# R151D.net
KiCad netlist of a schematic drawn in EAGLE
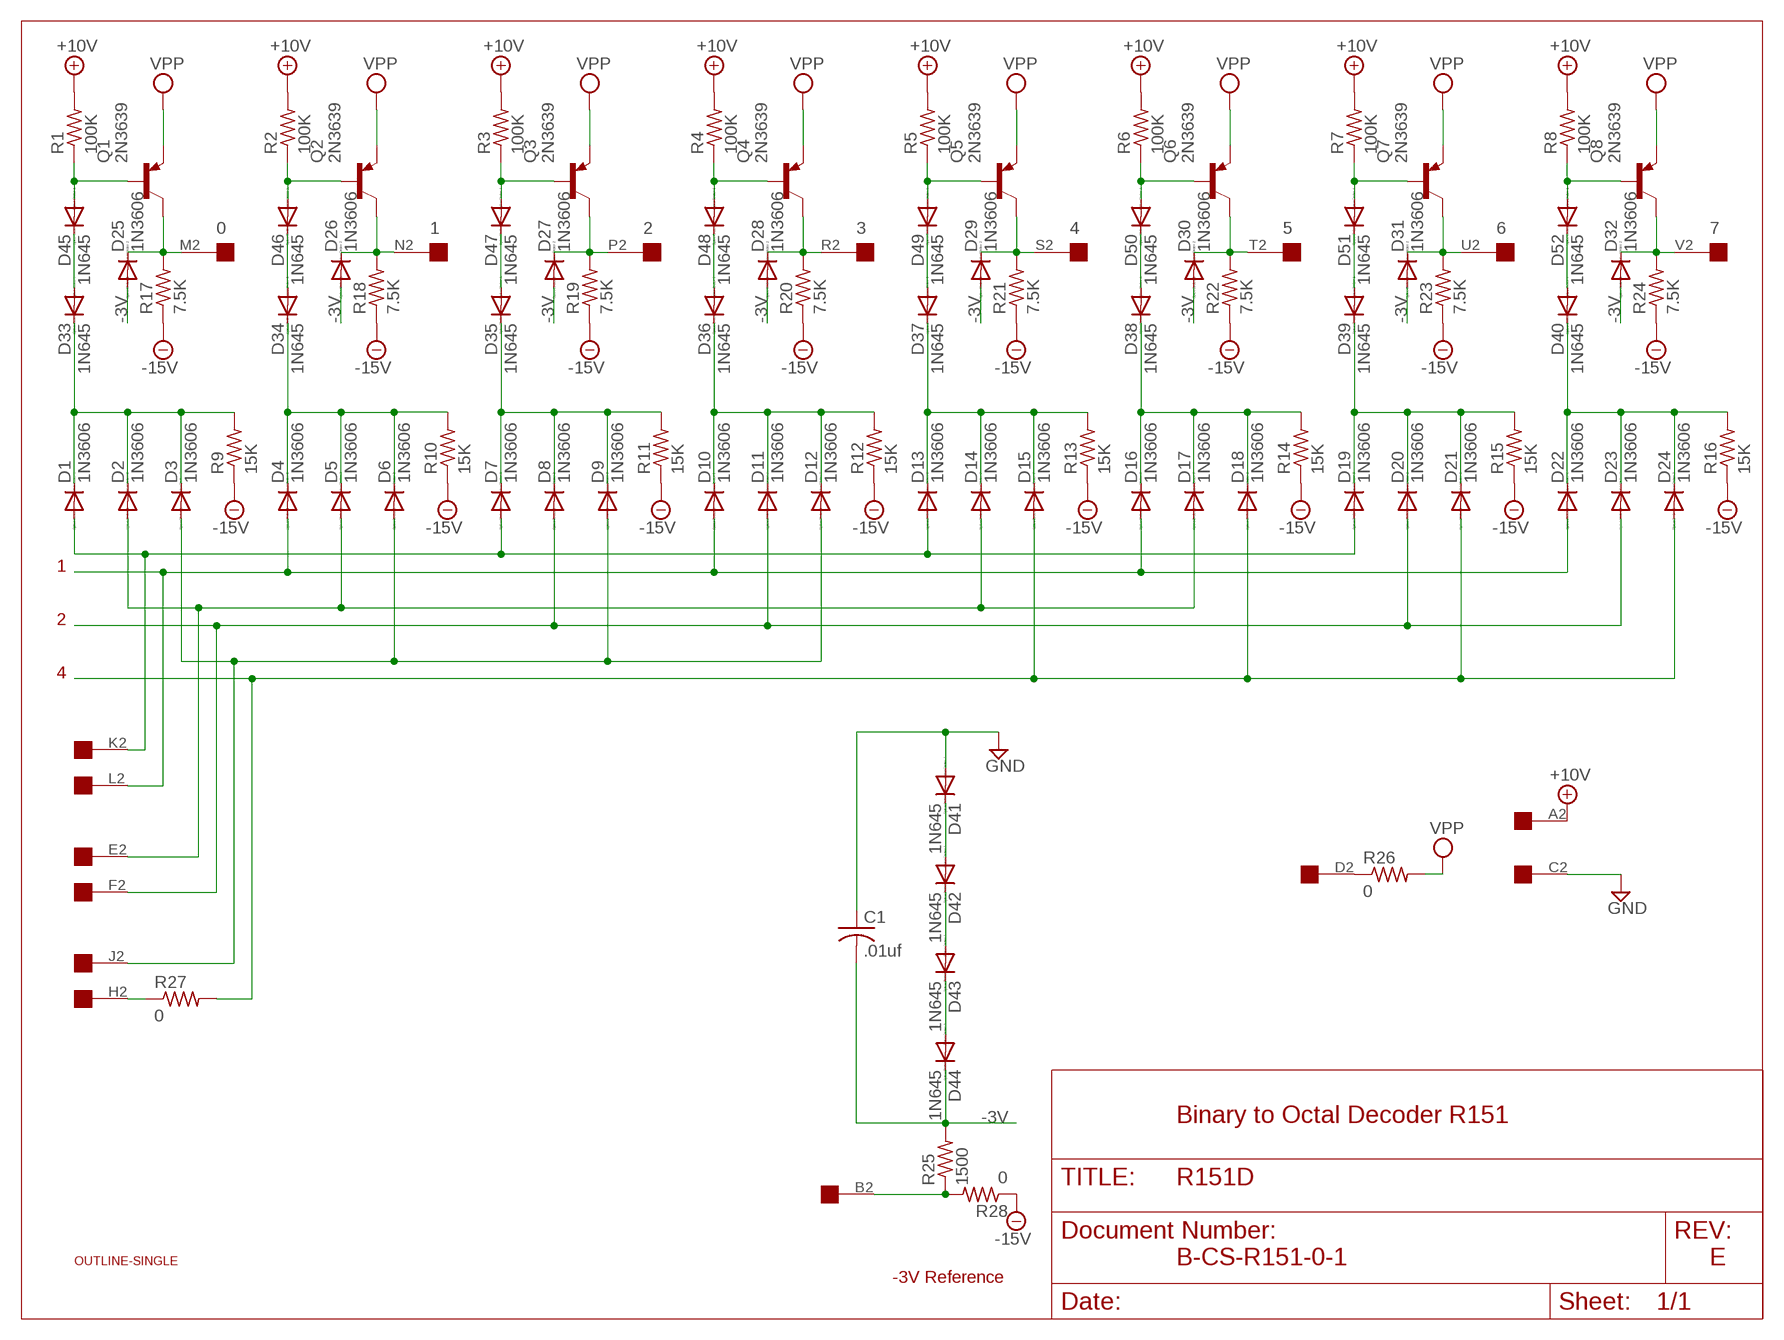
[diagram p0: schematic, sheet 1]

(export (version "E")
  (design (tool "Eeschema 10.0.6"))
  (components
    (comp (ref "C1")
      (value ".01uf")
      (footprint "eagle-import:C050-025X075")
      (libsource (lib "eagle-import") (part "C-US050-025X075"))
    )
    (comp (ref "D1")
      (value "1N3606")
      (footprint "eagle-import:DO35-10")
      (libsource (lib "eagle-import") (part "1N4148DO35-10"))
    )
    (comp (ref "D2")
      (value "1N3606")
      (footprint "eagle-import:DO35-10")
      (libsource (lib "eagle-import") (part "1N4148DO35-10"))
    )
    (comp (ref "D3")
      (value "1N3606")
      (footprint "eagle-import:DO35-10")
      (libsource (lib "eagle-import") (part "1N4148DO35-10"))
    )
    (comp (ref "D4")
      (value "1N3606")
      (footprint "eagle-import:DO35-10")
      (libsource (lib "eagle-import") (part "1N4148DO35-10"))
    )
    (comp (ref "D5")
      (value "1N3606")
      (footprint "eagle-import:DO35-10")
      (libsource (lib "eagle-import") (part "1N4148DO35-10"))
    )
    (comp (ref "D6")
      (value "1N3606")
      (footprint "eagle-import:DO35-10")
      (libsource (lib "eagle-import") (part "1N4148DO35-10"))
    )
    (comp (ref "D7")
      (value "1N3606")
      (footprint "eagle-import:DO35-10")
      (libsource (lib "eagle-import") (part "1N4148DO35-10"))
    )
    (comp (ref "D8")
      (value "1N3606")
      (footprint "eagle-import:DO35-10")
      (libsource (lib "eagle-import") (part "1N4148DO35-10"))
    )
    (comp (ref "D9")
      (value "1N3606")
      (footprint "eagle-import:DO35-10")
      (libsource (lib "eagle-import") (part "1N4148DO35-10"))
    )
    (comp (ref "D10")
      (value "1N3606")
      (footprint "eagle-import:DO35-10")
      (libsource (lib "eagle-import") (part "1N4148DO35-10"))
    )
    (comp (ref "D11")
      (value "1N3606")
      (footprint "eagle-import:DO35-10")
      (libsource (lib "eagle-import") (part "1N4148DO35-10"))
    )
    (comp (ref "D12")
      (value "1N3606")
      (footprint "eagle-import:DO35-10")
      (libsource (lib "eagle-import") (part "1N4148DO35-10"))
    )
    (comp (ref "D13")
      (value "1N3606")
      (footprint "eagle-import:DO35-10")
      (libsource (lib "eagle-import") (part "1N4148DO35-10"))
    )
    (comp (ref "D14")
      (value "1N3606")
      (footprint "eagle-import:DO35-10")
      (libsource (lib "eagle-import") (part "1N4148DO35-10"))
    )
    (comp (ref "D15")
      (value "1N3606")
      (footprint "eagle-import:DO35-10")
      (libsource (lib "eagle-import") (part "1N4148DO35-10"))
    )
    (comp (ref "D16")
      (value "1N3606")
      (footprint "eagle-import:DO35-10")
      (libsource (lib "eagle-import") (part "1N4148DO35-10"))
    )
    (comp (ref "D17")
      (value "1N3606")
      (footprint "eagle-import:DO35-10")
      (libsource (lib "eagle-import") (part "1N4148DO35-10"))
    )
    (comp (ref "D18")
      (value "1N3606")
      (footprint "eagle-import:DO35-10")
      (libsource (lib "eagle-import") (part "1N4148DO35-10"))
    )
    (comp (ref "D19")
      (value "1N3606")
      (footprint "eagle-import:DO35-10")
      (libsource (lib "eagle-import") (part "1N4148DO35-10"))
    )
    (comp (ref "D20")
      (value "1N3606")
      (footprint "eagle-import:DO35-10")
      (libsource (lib "eagle-import") (part "1N4148DO35-10"))
    )
    (comp (ref "D21")
      (value "1N3606")
      (footprint "eagle-import:DO35-10")
      (libsource (lib "eagle-import") (part "1N4148DO35-10"))
    )
    (comp (ref "D22")
      (value "1N3606")
      (footprint "eagle-import:DO35-10")
      (libsource (lib "eagle-import") (part "1N4148DO35-10"))
    )
    (comp (ref "D23")
      (value "1N3606")
      (footprint "eagle-import:DO35-10")
      (libsource (lib "eagle-import") (part "1N4148DO35-10"))
    )
    (comp (ref "D24")
      (value "1N3606")
      (footprint "eagle-import:DO35-10")
      (libsource (lib "eagle-import") (part "1N4148DO35-10"))
    )
    (comp (ref "D25")
      (value "1N3606")
      (footprint "eagle-import:DO35-10")
      (libsource (lib "eagle-import") (part "1N4148DO35-10"))
    )
    (comp (ref "D26")
      (value "1N3606")
      (footprint "eagle-import:DO35-10")
      (libsource (lib "eagle-import") (part "1N4148DO35-10"))
    )
    (comp (ref "D27")
      (value "1N3606")
      (footprint "eagle-import:DO35-10")
      (libsource (lib "eagle-import") (part "1N4148DO35-10"))
    )
    (comp (ref "D28")
      (value "1N3606")
      (footprint "eagle-import:DO35-10")
      (libsource (lib "eagle-import") (part "1N4148DO35-10"))
    )
    (comp (ref "D29")
      (value "1N3606")
      (footprint "eagle-import:DO35-10")
      (libsource (lib "eagle-import") (part "1N4148DO35-10"))
    )
    (comp (ref "D30")
      (value "1N3606")
      (footprint "eagle-import:DO35-10")
      (libsource (lib "eagle-import") (part "1N4148DO35-10"))
    )
    (comp (ref "D31")
      (value "1N3606")
      (footprint "eagle-import:DO35-10")
      (libsource (lib "eagle-import") (part "1N4148DO35-10"))
    )
    (comp (ref "D32")
      (value "1N3606")
      (footprint "eagle-import:DO35-10")
      (libsource (lib "eagle-import") (part "1N4148DO35-10"))
    )
    (comp (ref "D33")
      (value "1N645")
      (footprint "eagle-import:DO35-10")
      (libsource (lib "eagle-import") (part "1N4148DO35-10"))
    )
    (comp (ref "D34")
      (value "1N645")
      (footprint "eagle-import:DO35-10")
      (libsource (lib "eagle-import") (part "1N4148DO35-10"))
    )
    (comp (ref "D35")
      (value "1N645")
      (footprint "eagle-import:DO35-10")
      (libsource (lib "eagle-import") (part "1N4148DO35-10"))
    )
    (comp (ref "D36")
      (value "1N645")
      (footprint "eagle-import:DO35-10")
      (libsource (lib "eagle-import") (part "1N4148DO35-10"))
    )
    (comp (ref "D37")
      (value "1N645")
      (footprint "eagle-import:DO35-10")
      (libsource (lib "eagle-import") (part "1N4148DO35-10"))
    )
    (comp (ref "D38")
      (value "1N645")
      (footprint "eagle-import:DO35-10")
      (libsource (lib "eagle-import") (part "1N4148DO35-10"))
    )
    (comp (ref "D39")
      (value "1N645")
      (footprint "eagle-import:DO35-10")
      (libsource (lib "eagle-import") (part "1N4148DO35-10"))
    )
    (comp (ref "D40")
      (value "1N645")
      (footprint "eagle-import:DO35-10")
      (libsource (lib "eagle-import") (part "1N4148DO35-10"))
    )
    (comp (ref "D41")
      (value "1N645")
      (footprint "eagle-import:DO35-10")
      (libsource (lib "eagle-import") (part "1N4148DO35-10"))
    )
    (comp (ref "D42")
      (value "1N645")
      (footprint "eagle-import:DO35-10")
      (libsource (lib "eagle-import") (part "1N4148DO35-10"))
    )
    (comp (ref "D43")
      (value "1N645")
      (footprint "eagle-import:DO35-10")
      (libsource (lib "eagle-import") (part "1N4148DO35-10"))
    )
    (comp (ref "D44")
      (value "1N645")
      (footprint "eagle-import:DO35-10")
      (libsource (lib "eagle-import") (part "1N4148DO35-10"))
    )
    (comp (ref "D45")
      (value "1N645")
      (footprint "eagle-import:DO35-10")
      (libsource (lib "eagle-import") (part "1N4148DO35-10"))
    )
    (comp (ref "D46")
      (value "1N645")
      (footprint "eagle-import:DO35-10")
      (libsource (lib "eagle-import") (part "1N4148DO35-10"))
    )
    (comp (ref "D47")
      (value "1N645")
      (footprint "eagle-import:DO35-10")
      (libsource (lib "eagle-import") (part "1N4148DO35-10"))
    )
    (comp (ref "D48")
      (value "1N645")
      (footprint "eagle-import:DO35-10")
      (libsource (lib "eagle-import") (part "1N4148DO35-10"))
    )
    (comp (ref "D49")
      (value "1N645")
      (footprint "eagle-import:DO35-10")
      (libsource (lib "eagle-import") (part "1N4148DO35-10"))
    )
    (comp (ref "D50")
      (value "1N645")
      (footprint "eagle-import:DO35-10")
      (libsource (lib "eagle-import") (part "1N4148DO35-10"))
    )
    (comp (ref "D51")
      (value "1N645")
      (footprint "eagle-import:DO35-10")
      (libsource (lib "eagle-import") (part "1N4148DO35-10"))
    )
    (comp (ref "D52")
      (value "1N645")
      (footprint "eagle-import:DO35-10")
      (libsource (lib "eagle-import") (part "1N4148DO35-10"))
    )
    (comp (ref "Q1")
      (value "2N3639")
      (footprint "eagle-import:TO39")
      (libsource (lib "eagle-import") (part "2N3637"))
    )
    (comp (ref "Q2")
      (value "2N3639")
      (footprint "eagle-import:TO39")
      (libsource (lib "eagle-import") (part "2N3637"))
    )
    (comp (ref "Q3")
      (value "2N3639")
      (footprint "eagle-import:TO39")
      (libsource (lib "eagle-import") (part "2N3637"))
    )
    (comp (ref "Q4")
      (value "2N3639")
      (footprint "eagle-import:TO39")
      (libsource (lib "eagle-import") (part "2N3637"))
    )
    (comp (ref "Q5")
      (value "2N3639")
      (footprint "eagle-import:TO39")
      (libsource (lib "eagle-import") (part "2N3637"))
    )
    (comp (ref "Q6")
      (value "2N3639")
      (footprint "eagle-import:TO39")
      (libsource (lib "eagle-import") (part "2N3637"))
    )
    (comp (ref "Q7")
      (value "2N3639")
      (footprint "eagle-import:TO39")
      (libsource (lib "eagle-import") (part "2N3637"))
    )
    (comp (ref "Q8")
      (value "2N3639")
      (footprint "eagle-import:TO39")
      (libsource (lib "eagle-import") (part "2N3637"))
    )
    (comp (ref "R1")
      (value "100K")
      (footprint "eagle-import:0207_10")
      (libsource (lib "eagle-import") (part "R-US_0207/10"))
    )
    (comp (ref "R2")
      (value "100K")
      (footprint "eagle-import:0207_10")
      (libsource (lib "eagle-import") (part "R-US_0207/10"))
    )
    (comp (ref "R3")
      (value "100K")
      (footprint "eagle-import:0207_10")
      (libsource (lib "eagle-import") (part "R-US_0207/10"))
    )
    (comp (ref "R4")
      (value "100K")
      (footprint "eagle-import:0207_10")
      (libsource (lib "eagle-import") (part "R-US_0207/10"))
    )
    (comp (ref "R5")
      (value "100K")
      (footprint "eagle-import:0207_10")
      (libsource (lib "eagle-import") (part "R-US_0207/10"))
    )
    (comp (ref "R6")
      (value "100K")
      (footprint "eagle-import:0207_10")
      (libsource (lib "eagle-import") (part "R-US_0207/10"))
    )
    (comp (ref "R7")
      (value "100K")
      (footprint "eagle-import:0207_10")
      (libsource (lib "eagle-import") (part "R-US_0207/10"))
    )
    (comp (ref "R8")
      (value "100K")
      (footprint "eagle-import:0207_10")
      (libsource (lib "eagle-import") (part "R-US_0207/10"))
    )
    (comp (ref "R9")
      (value "15K")
      (footprint "eagle-import:0207_10")
      (libsource (lib "eagle-import") (part "R-US_0207/10"))
    )
    (comp (ref "R10")
      (value "15K")
      (footprint "eagle-import:0207_10")
      (libsource (lib "eagle-import") (part "R-US_0207/10"))
    )
    (comp (ref "R11")
      (value "15K")
      (footprint "eagle-import:0207_10")
      (libsource (lib "eagle-import") (part "R-US_0207/10"))
    )
    (comp (ref "R12")
      (value "15K")
      (footprint "eagle-import:0207_10")
      (libsource (lib "eagle-import") (part "R-US_0207/10"))
    )
    (comp (ref "R13")
      (value "15K")
      (footprint "eagle-import:0207_10")
      (libsource (lib "eagle-import") (part "R-US_0207/10"))
    )
    (comp (ref "R14")
      (value "15K")
      (footprint "eagle-import:0207_10")
      (libsource (lib "eagle-import") (part "R-US_0207/10"))
    )
    (comp (ref "R15")
      (value "15K")
      (footprint "eagle-import:0207_10")
      (libsource (lib "eagle-import") (part "R-US_0207/10"))
    )
    (comp (ref "R16")
      (value "15K")
      (footprint "eagle-import:0207_10")
      (libsource (lib "eagle-import") (part "R-US_0207/10"))
    )
    (comp (ref "R17")
      (value "7.5K")
      (footprint "eagle-import:0207_10")
      (libsource (lib "eagle-import") (part "R-US_0207/10"))
    )
    (comp (ref "R18")
      (value "7.5K")
      (footprint "eagle-import:0207_10")
      (libsource (lib "eagle-import") (part "R-US_0207/10"))
    )
    (comp (ref "R19")
      (value "7.5K")
      (footprint "eagle-import:0207_10")
      (libsource (lib "eagle-import") (part "R-US_0207/10"))
    )
    (comp (ref "R20")
      (value "7.5K")
      (footprint "eagle-import:0207_10")
      (libsource (lib "eagle-import") (part "R-US_0207/10"))
    )
    (comp (ref "R21")
      (value "7.5K")
      (footprint "eagle-import:0207_10")
      (libsource (lib "eagle-import") (part "R-US_0207/10"))
    )
    (comp (ref "R22")
      (value "7.5K")
      (footprint "eagle-import:0207_10")
      (libsource (lib "eagle-import") (part "R-US_0207/10"))
    )
    (comp (ref "R23")
      (value "7.5K")
      (footprint "eagle-import:0207_10")
      (libsource (lib "eagle-import") (part "R-US_0207/10"))
    )
    (comp (ref "R24")
      (value "7.5K")
      (footprint "eagle-import:0207_10")
      (libsource (lib "eagle-import") (part "R-US_0207/10"))
    )
    (comp (ref "R25")
      (value "1500")
      (footprint "eagle-import:0207_10")
      (libsource (lib "eagle-import") (part "R-US_0207/10"))
    )
    (comp (ref "R26")
      (value "0")
      (footprint "eagle-import:0207_10")
      (libsource (lib "eagle-import") (part "R-US_0207/10"))
    )
    (comp (ref "R27")
      (value "0")
      (footprint "eagle-import:0207_10")
      (libsource (lib "eagle-import") (part "R-US_0207/10"))
    )
    (comp (ref "R28")
      (value "0")
      (footprint "eagle-import:0207_10")
      (libsource (lib "eagle-import") (part "R-US_0207/10"))
    )
    (comp (ref "U$1")
      (value "OUTLINE-SINGLE")
      (footprint "eagle-import:SINGLE")
      (libsource (lib "eagle-import") (part "OUTLINE-SINGLE"))
    )
    (comp (ref "U$2")
      (value "EDGE-1")
      (footprint "eagle-import:EDGE-CON1")
      (libsource (lib "eagle-import") (part "EDGE-1"))
    )
  )
  (nets
    (net (code "1") (name "+10V") (class "Default")
      (node (ref "R1") (pin "2") (pinfunction "2_2") (pintype "passive"))
      (node (ref "R2") (pin "2") (pinfunction "2_2") (pintype "passive"))
      (node (ref "R3") (pin "2") (pinfunction "2_2") (pintype "passive"))
      (node (ref "R4") (pin "2") (pinfunction "2_2") (pintype "passive"))
      (node (ref "R5") (pin "2") (pinfunction "2_2") (pintype "passive"))
      (node (ref "R6") (pin "2") (pinfunction "2_2") (pintype "passive"))
      (node (ref "R7") (pin "2") (pinfunction "2_2") (pintype "passive"))
      (node (ref "R8") (pin "2") (pinfunction "2_2") (pintype "passive"))
      (node (ref "U$2") (pin "A2") (pinfunction "1_A2") (pintype "bidirectional"))
    )
    (net (code "2") (name "-15V") (class "Default")
      (node (ref "R10") (pin "1") (pinfunction "1_1") (pintype "passive"))
      (node (ref "R11") (pin "1") (pinfunction "1_1") (pintype "passive"))
      (node (ref "R12") (pin "1") (pinfunction "1_1") (pintype "passive"))
      (node (ref "R13") (pin "1") (pinfunction "1_1") (pintype "passive"))
      (node (ref "R14") (pin "1") (pinfunction "1_1") (pintype "passive"))
      (node (ref "R15") (pin "1") (pinfunction "1_1") (pintype "passive"))
      (node (ref "R16") (pin "1") (pinfunction "1_1") (pintype "passive"))
      (node (ref "R17") (pin "1") (pinfunction "1_1") (pintype "passive"))
      (node (ref "R18") (pin "1") (pinfunction "1_1") (pintype "passive"))
      (node (ref "R19") (pin "1") (pinfunction "1_1") (pintype "passive"))
      (node (ref "R20") (pin "1") (pinfunction "1_1") (pintype "passive"))
      (node (ref "R21") (pin "1") (pinfunction "1_1") (pintype "passive"))
      (node (ref "R22") (pin "1") (pinfunction "1_1") (pintype "passive"))
      (node (ref "R23") (pin "1") (pinfunction "1_1") (pintype "passive"))
      (node (ref "R24") (pin "1") (pinfunction "1_1") (pintype "passive"))
      (node (ref "R28") (pin "1") (pinfunction "1_1") (pintype "passive"))
      (node (ref "R9") (pin "1") (pinfunction "1_1") (pintype "passive"))
    )
    (net (code "3") (name "/-3V") (class "Default")
      (node (ref "C1") (pin "2") (pinfunction "2_2") (pintype "passive"))
      (node (ref "D25") (pin "A") (pinfunction "A_A") (pintype "passive"))
      (node (ref "D26") (pin "A") (pinfunction "A_A") (pintype "passive"))
      (node (ref "D27") (pin "A") (pinfunction "A_A") (pintype "passive"))
      (node (ref "D28") (pin "A") (pinfunction "A_A") (pintype "passive"))
      (node (ref "D29") (pin "A") (pinfunction "A_A") (pintype "passive"))
      (node (ref "D30") (pin "A") (pinfunction "A_A") (pintype "passive"))
      (node (ref "D31") (pin "A") (pinfunction "A_A") (pintype "passive"))
      (node (ref "D32") (pin "A") (pinfunction "A_A") (pintype "passive"))
      (node (ref "D44") (pin "C") (pinfunction "C_C") (pintype "passive"))
      (node (ref "R25") (pin "2") (pinfunction "2_2") (pintype "passive"))
    )
    (net (code "4") (name "/0") (class "Default")
      (node (ref "D25") (pin "C") (pinfunction "C_C") (pintype "passive"))
      (node (ref "Q1") (pin "3") (pinfunction "C_3") (pintype "passive"))
      (node (ref "R17") (pin "2") (pinfunction "2_2") (pintype "passive"))
      (node (ref "U$2") (pin "M2") (pinfunction "1_M2") (pintype "bidirectional"))
    )
    (net (code "5") (name "/1") (class "Default")
      (node (ref "D26") (pin "C") (pinfunction "C_C") (pintype "passive"))
      (node (ref "Q2") (pin "3") (pinfunction "C_3") (pintype "passive"))
      (node (ref "R18") (pin "2") (pinfunction "2_2") (pintype "passive"))
      (node (ref "U$2") (pin "N2") (pinfunction "1_N2") (pintype "bidirectional"))
    )
    (net (code "6") (name "/2") (class "Default")
      (node (ref "D27") (pin "C") (pinfunction "C_C") (pintype "passive"))
      (node (ref "Q3") (pin "3") (pinfunction "C_3") (pintype "passive"))
      (node (ref "R19") (pin "2") (pinfunction "2_2") (pintype "passive"))
      (node (ref "U$2") (pin "P2") (pinfunction "1_P2") (pintype "bidirectional"))
    )
    (net (code "7") (name "/3") (class "Default")
      (node (ref "D28") (pin "C") (pinfunction "C_C") (pintype "passive"))
      (node (ref "Q4") (pin "3") (pinfunction "C_3") (pintype "passive"))
      (node (ref "R20") (pin "2") (pinfunction "2_2") (pintype "passive"))
      (node (ref "U$2") (pin "R2") (pinfunction "1_R2") (pintype "bidirectional"))
    )
    (net (code "8") (name "/4") (class "Default")
      (node (ref "D29") (pin "C") (pinfunction "C_C") (pintype "passive"))
      (node (ref "Q5") (pin "3") (pinfunction "C_3") (pintype "passive"))
      (node (ref "R21") (pin "2") (pinfunction "2_2") (pintype "passive"))
      (node (ref "U$2") (pin "S2") (pinfunction "1_S2") (pintype "bidirectional"))
    )
    (net (code "9") (name "/5") (class "Default")
      (node (ref "D30") (pin "C") (pinfunction "C_C") (pintype "passive"))
      (node (ref "Q6") (pin "3") (pinfunction "C_3") (pintype "passive"))
      (node (ref "R22") (pin "2") (pinfunction "2_2") (pintype "passive"))
      (node (ref "U$2") (pin "T2") (pinfunction "1_T2") (pintype "bidirectional"))
    )
    (net (code "10") (name "/6") (class "Default")
      (node (ref "D31") (pin "C") (pinfunction "C_C") (pintype "passive"))
      (node (ref "Q7") (pin "3") (pinfunction "C_3") (pintype "passive"))
      (node (ref "R23") (pin "2") (pinfunction "2_2") (pintype "passive"))
      (node (ref "U$2") (pin "U2") (pinfunction "1_U2") (pintype "bidirectional"))
    )
    (net (code "11") (name "/7") (class "Default")
      (node (ref "D32") (pin "C") (pinfunction "C_C") (pintype "passive"))
      (node (ref "Q8") (pin "3") (pinfunction "C_3") (pintype "passive"))
      (node (ref "R24") (pin "2") (pinfunction "2_2") (pintype "passive"))
      (node (ref "U$2") (pin "V2") (pinfunction "1_V2") (pintype "bidirectional"))
    )
    (net (code "12") (name "GND") (class "Default")
      (node (ref "C1") (pin "1") (pinfunction "1_1") (pintype "passive"))
      (node (ref "D41") (pin "A") (pinfunction "A_A") (pintype "passive"))
      (node (ref "U$2") (pin "C2") (pinfunction "1_C2") (pintype "bidirectional"))
    )
    (net (code "13") (name "Net-(D1-PadC)") (class "Default")
      (node (ref "D1") (pin "C") (pinfunction "C_C") (pintype "passive"))
      (node (ref "D2") (pin "C") (pinfunction "C_C") (pintype "passive"))
      (node (ref "D3") (pin "C") (pinfunction "C_C") (pintype "passive"))
      (node (ref "D33") (pin "C") (pinfunction "C_C") (pintype "passive"))
      (node (ref "R9") (pin "2") (pinfunction "2_2") (pintype "passive"))
    )
    (net (code "14") (name "Net-(D10-PadC)") (class "Default")
      (node (ref "D10") (pin "C") (pinfunction "C_C") (pintype "passive"))
      (node (ref "D11") (pin "C") (pinfunction "C_C") (pintype "passive"))
      (node (ref "D12") (pin "C") (pinfunction "C_C") (pintype "passive"))
      (node (ref "D36") (pin "C") (pinfunction "C_C") (pintype "passive"))
      (node (ref "R12") (pin "2") (pinfunction "2_2") (pintype "passive"))
    )
    (net (code "15") (name "Net-(D13-PadC)") (class "Default")
      (node (ref "D13") (pin "C") (pinfunction "C_C") (pintype "passive"))
      (node (ref "D14") (pin "C") (pinfunction "C_C") (pintype "passive"))
      (node (ref "D15") (pin "C") (pinfunction "C_C") (pintype "passive"))
      (node (ref "D37") (pin "C") (pinfunction "C_C") (pintype "passive"))
      (node (ref "R13") (pin "2") (pinfunction "2_2") (pintype "passive"))
    )
    (net (code "16") (name "Net-(D15-PadA)") (class "Default")
      (node (ref "D15") (pin "A") (pinfunction "A_A") (pintype "passive"))
      (node (ref "D18") (pin "A") (pinfunction "A_A") (pintype "passive"))
      (node (ref "D21") (pin "A") (pinfunction "A_A") (pintype "passive"))
      (node (ref "D24") (pin "A") (pinfunction "A_A") (pintype "passive"))
      (node (ref "R27") (pin "2") (pinfunction "2_2") (pintype "passive"))
    )
    (net (code "17") (name "Net-(D16-PadC)") (class "Default")
      (node (ref "D16") (pin "C") (pinfunction "C_C") (pintype "passive"))
      (node (ref "D17") (pin "C") (pinfunction "C_C") (pintype "passive"))
      (node (ref "D18") (pin "C") (pinfunction "C_C") (pintype "passive"))
      (node (ref "D38") (pin "C") (pinfunction "C_C") (pintype "passive"))
      (node (ref "R14") (pin "2") (pinfunction "2_2") (pintype "passive"))
    )
    (net (code "18") (name "Net-(D19-PadC)") (class "Default")
      (node (ref "D19") (pin "C") (pinfunction "C_C") (pintype "passive"))
      (node (ref "D20") (pin "C") (pinfunction "C_C") (pintype "passive"))
      (node (ref "D21") (pin "C") (pinfunction "C_C") (pintype "passive"))
      (node (ref "D39") (pin "C") (pinfunction "C_C") (pintype "passive"))
      (node (ref "R15") (pin "2") (pinfunction "2_2") (pintype "passive"))
    )
    (net (code "19") (name "Net-(D22-PadC)") (class "Default")
      (node (ref "D22") (pin "C") (pinfunction "C_C") (pintype "passive"))
      (node (ref "D23") (pin "C") (pinfunction "C_C") (pintype "passive"))
      (node (ref "D24") (pin "C") (pinfunction "C_C") (pintype "passive"))
      (node (ref "D40") (pin "C") (pinfunction "C_C") (pintype "passive"))
      (node (ref "R16") (pin "2") (pinfunction "2_2") (pintype "passive"))
    )
    (net (code "20") (name "Net-(D33-PadA)") (class "Default")
      (node (ref "D33") (pin "A") (pinfunction "A_A") (pintype "passive"))
      (node (ref "D45") (pin "C") (pinfunction "C_C") (pintype "passive"))
    )
    (net (code "21") (name "Net-(D34-PadA)") (class "Default")
      (node (ref "D34") (pin "A") (pinfunction "A_A") (pintype "passive"))
      (node (ref "D46") (pin "C") (pinfunction "C_C") (pintype "passive"))
    )
    (net (code "22") (name "Net-(D34-PadC)") (class "Default")
      (node (ref "D34") (pin "C") (pinfunction "C_C") (pintype "passive"))
      (node (ref "D4") (pin "C") (pinfunction "C_C") (pintype "passive"))
      (node (ref "D5") (pin "C") (pinfunction "C_C") (pintype "passive"))
      (node (ref "D6") (pin "C") (pinfunction "C_C") (pintype "passive"))
      (node (ref "R10") (pin "2") (pinfunction "2_2") (pintype "passive"))
    )
    (net (code "23") (name "Net-(D35-PadA)") (class "Default")
      (node (ref "D35") (pin "A") (pinfunction "A_A") (pintype "passive"))
      (node (ref "D47") (pin "C") (pinfunction "C_C") (pintype "passive"))
    )
    (net (code "24") (name "Net-(D35-PadC)") (class "Default")
      (node (ref "D35") (pin "C") (pinfunction "C_C") (pintype "passive"))
      (node (ref "D7") (pin "C") (pinfunction "C_C") (pintype "passive"))
      (node (ref "D8") (pin "C") (pinfunction "C_C") (pintype "passive"))
      (node (ref "D9") (pin "C") (pinfunction "C_C") (pintype "passive"))
      (node (ref "R11") (pin "2") (pinfunction "2_2") (pintype "passive"))
    )
    (net (code "25") (name "Net-(D36-PadA)") (class "Default")
      (node (ref "D36") (pin "A") (pinfunction "A_A") (pintype "passive"))
      (node (ref "D48") (pin "C") (pinfunction "C_C") (pintype "passive"))
    )
    (net (code "26") (name "Net-(D37-PadA)") (class "Default")
      (node (ref "D37") (pin "A") (pinfunction "A_A") (pintype "passive"))
      (node (ref "D49") (pin "C") (pinfunction "C_C") (pintype "passive"))
    )
    (net (code "27") (name "Net-(D38-PadA)") (class "Default")
      (node (ref "D38") (pin "A") (pinfunction "A_A") (pintype "passive"))
      (node (ref "D50") (pin "C") (pinfunction "C_C") (pintype "passive"))
    )
    (net (code "28") (name "Net-(D39-PadA)") (class "Default")
      (node (ref "D39") (pin "A") (pinfunction "A_A") (pintype "passive"))
      (node (ref "D51") (pin "C") (pinfunction "C_C") (pintype "passive"))
    )
    (net (code "29") (name "Net-(D40-PadA)") (class "Default")
      (node (ref "D40") (pin "A") (pinfunction "A_A") (pintype "passive"))
      (node (ref "D52") (pin "C") (pinfunction "C_C") (pintype "passive"))
    )
    (net (code "30") (name "Net-(D41-PadC)") (class "Default")
      (node (ref "D41") (pin "C") (pinfunction "C_C") (pintype "passive"))
      (node (ref "D42") (pin "A") (pinfunction "A_A") (pintype "passive"))
    )
    (net (code "31") (name "Net-(D42-PadC)") (class "Default")
      (node (ref "D42") (pin "C") (pinfunction "C_C") (pintype "passive"))
      (node (ref "D43") (pin "A") (pinfunction "A_A") (pintype "passive"))
    )
    (net (code "32") (name "Net-(D43-PadC)") (class "Default")
      (node (ref "D43") (pin "C") (pinfunction "C_C") (pintype "passive"))
      (node (ref "D44") (pin "A") (pinfunction "A_A") (pintype "passive"))
    )
    (net (code "33") (name "Net-(Q1-B)") (class "Default")
      (node (ref "D45") (pin "A") (pinfunction "A_A") (pintype "passive"))
      (node (ref "Q1") (pin "2") (pinfunction "B_2") (pintype "passive"))
      (node (ref "R1") (pin "1") (pinfunction "1_1") (pintype "passive"))
    )
    (net (code "34") (name "Net-(Q2-B)") (class "Default")
      (node (ref "D46") (pin "A") (pinfunction "A_A") (pintype "passive"))
      (node (ref "Q2") (pin "2") (pinfunction "B_2") (pintype "passive"))
      (node (ref "R2") (pin "1") (pinfunction "1_1") (pintype "passive"))
    )
    (net (code "35") (name "Net-(Q3-B)") (class "Default")
      (node (ref "D47") (pin "A") (pinfunction "A_A") (pintype "passive"))
      (node (ref "Q3") (pin "2") (pinfunction "B_2") (pintype "passive"))
      (node (ref "R3") (pin "1") (pinfunction "1_1") (pintype "passive"))
    )
    (net (code "36") (name "Net-(Q4-B)") (class "Default")
      (node (ref "D48") (pin "A") (pinfunction "A_A") (pintype "passive"))
      (node (ref "Q4") (pin "2") (pinfunction "B_2") (pintype "passive"))
      (node (ref "R4") (pin "1") (pinfunction "1_1") (pintype "passive"))
    )
    (net (code "37") (name "Net-(Q5-B)") (class "Default")
      (node (ref "D49") (pin "A") (pinfunction "A_A") (pintype "passive"))
      (node (ref "Q5") (pin "2") (pinfunction "B_2") (pintype "passive"))
      (node (ref "R5") (pin "1") (pinfunction "1_1") (pintype "passive"))
    )
    (net (code "38") (name "Net-(Q6-B)") (class "Default")
      (node (ref "D50") (pin "A") (pinfunction "A_A") (pintype "passive"))
      (node (ref "Q6") (pin "2") (pinfunction "B_2") (pintype "passive"))
      (node (ref "R6") (pin "1") (pinfunction "1_1") (pintype "passive"))
    )
    (net (code "39") (name "Net-(Q7-B)") (class "Default")
      (node (ref "D51") (pin "A") (pinfunction "A_A") (pintype "passive"))
      (node (ref "Q7") (pin "2") (pinfunction "B_2") (pintype "passive"))
      (node (ref "R7") (pin "1") (pinfunction "1_1") (pintype "passive"))
    )
    (net (code "40") (name "Net-(Q8-B)") (class "Default")
      (node (ref "D52") (pin "A") (pinfunction "A_A") (pintype "passive"))
      (node (ref "Q8") (pin "2") (pinfunction "B_2") (pintype "passive"))
      (node (ref "R8") (pin "1") (pinfunction "1_1") (pintype "passive"))
    )
    (net (code "41") (name "Net-(U$2B-1)") (class "Default")
      (node (ref "R25") (pin "1") (pinfunction "1_1") (pintype "passive"))
      (node (ref "R28") (pin "2") (pinfunction "2_2") (pintype "passive"))
      (node (ref "U$2") (pin "B2") (pinfunction "1_B2") (pintype "bidirectional"))
    )
    (net (code "42") (name "Net-(U$2D-1)") (class "Default")
      (node (ref "R26") (pin "1") (pinfunction "1_1") (pintype "passive"))
      (node (ref "U$2") (pin "D2") (pinfunction "1_D2") (pintype "bidirectional"))
    )
    (net (code "43") (name "Net-(U$2E-1)") (class "Default")
      (node (ref "D14") (pin "A") (pinfunction "A_A") (pintype "passive"))
      (node (ref "D17") (pin "A") (pinfunction "A_A") (pintype "passive"))
      (node (ref "D2") (pin "A") (pinfunction "A_A") (pintype "passive"))
      (node (ref "D5") (pin "A") (pinfunction "A_A") (pintype "passive"))
      (node (ref "U$2") (pin "E2") (pinfunction "1_E2") (pintype "bidirectional"))
    )
    (net (code "44") (name "Net-(U$2F-1)") (class "Default")
      (node (ref "D11") (pin "A") (pinfunction "A_A") (pintype "passive"))
      (node (ref "D20") (pin "A") (pinfunction "A_A") (pintype "passive"))
      (node (ref "D23") (pin "A") (pinfunction "A_A") (pintype "passive"))
      (node (ref "D8") (pin "A") (pinfunction "A_A") (pintype "passive"))
      (node (ref "U$2") (pin "F2") (pinfunction "1_F2") (pintype "bidirectional"))
    )
    (net (code "45") (name "Net-(U$2G-1)") (class "Default")
      (node (ref "R27") (pin "1") (pinfunction "1_1") (pintype "passive"))
      (node (ref "U$2") (pin "H2") (pinfunction "1_H2") (pintype "bidirectional"))
    )
    (net (code "46") (name "Net-(U$2H-1)") (class "Default")
      (node (ref "D12") (pin "A") (pinfunction "A_A") (pintype "passive"))
      (node (ref "D3") (pin "A") (pinfunction "A_A") (pintype "passive"))
      (node (ref "D6") (pin "A") (pinfunction "A_A") (pintype "passive"))
      (node (ref "D9") (pin "A") (pinfunction "A_A") (pintype "passive"))
      (node (ref "U$2") (pin "J2") (pinfunction "1_J2") (pintype "bidirectional"))
    )
    (net (code "47") (name "Net-(U$2I-1)") (class "Default")
      (node (ref "D1") (pin "A") (pinfunction "A_A") (pintype "passive"))
      (node (ref "D13") (pin "A") (pinfunction "A_A") (pintype "passive"))
      (node (ref "D19") (pin "A") (pinfunction "A_A") (pintype "passive"))
      (node (ref "D7") (pin "A") (pinfunction "A_A") (pintype "passive"))
      (node (ref "U$2") (pin "K2") (pinfunction "1_K2") (pintype "bidirectional"))
    )
    (net (code "48") (name "Net-(U$2J-1)") (class "Default")
      (node (ref "D10") (pin "A") (pinfunction "A_A") (pintype "passive"))
      (node (ref "D16") (pin "A") (pinfunction "A_A") (pintype "passive"))
      (node (ref "D22") (pin "A") (pinfunction "A_A") (pintype "passive"))
      (node (ref "D4") (pin "A") (pinfunction "A_A") (pintype "passive"))
      (node (ref "U$2") (pin "L2") (pinfunction "1_L2") (pintype "bidirectional"))
    )
    (net (code "49") (name "VPP") (class "Default")
      (node (ref "Q1") (pin "1") (pinfunction "E_1") (pintype "passive"))
      (node (ref "Q2") (pin "1") (pinfunction "E_1") (pintype "passive"))
      (node (ref "Q3") (pin "1") (pinfunction "E_1") (pintype "passive"))
      (node (ref "Q4") (pin "1") (pinfunction "E_1") (pintype "passive"))
      (node (ref "Q5") (pin "1") (pinfunction "E_1") (pintype "passive"))
      (node (ref "Q6") (pin "1") (pinfunction "E_1") (pintype "passive"))
      (node (ref "Q7") (pin "1") (pinfunction "E_1") (pintype "passive"))
      (node (ref "Q8") (pin "1") (pinfunction "E_1") (pintype "passive"))
      (node (ref "R26") (pin "2") (pinfunction "2_2") (pintype "passive"))
    )
  )
)
